# 2_MCU_schdoc.net
KiCad netlist of a schematic drawn in Altium Designer
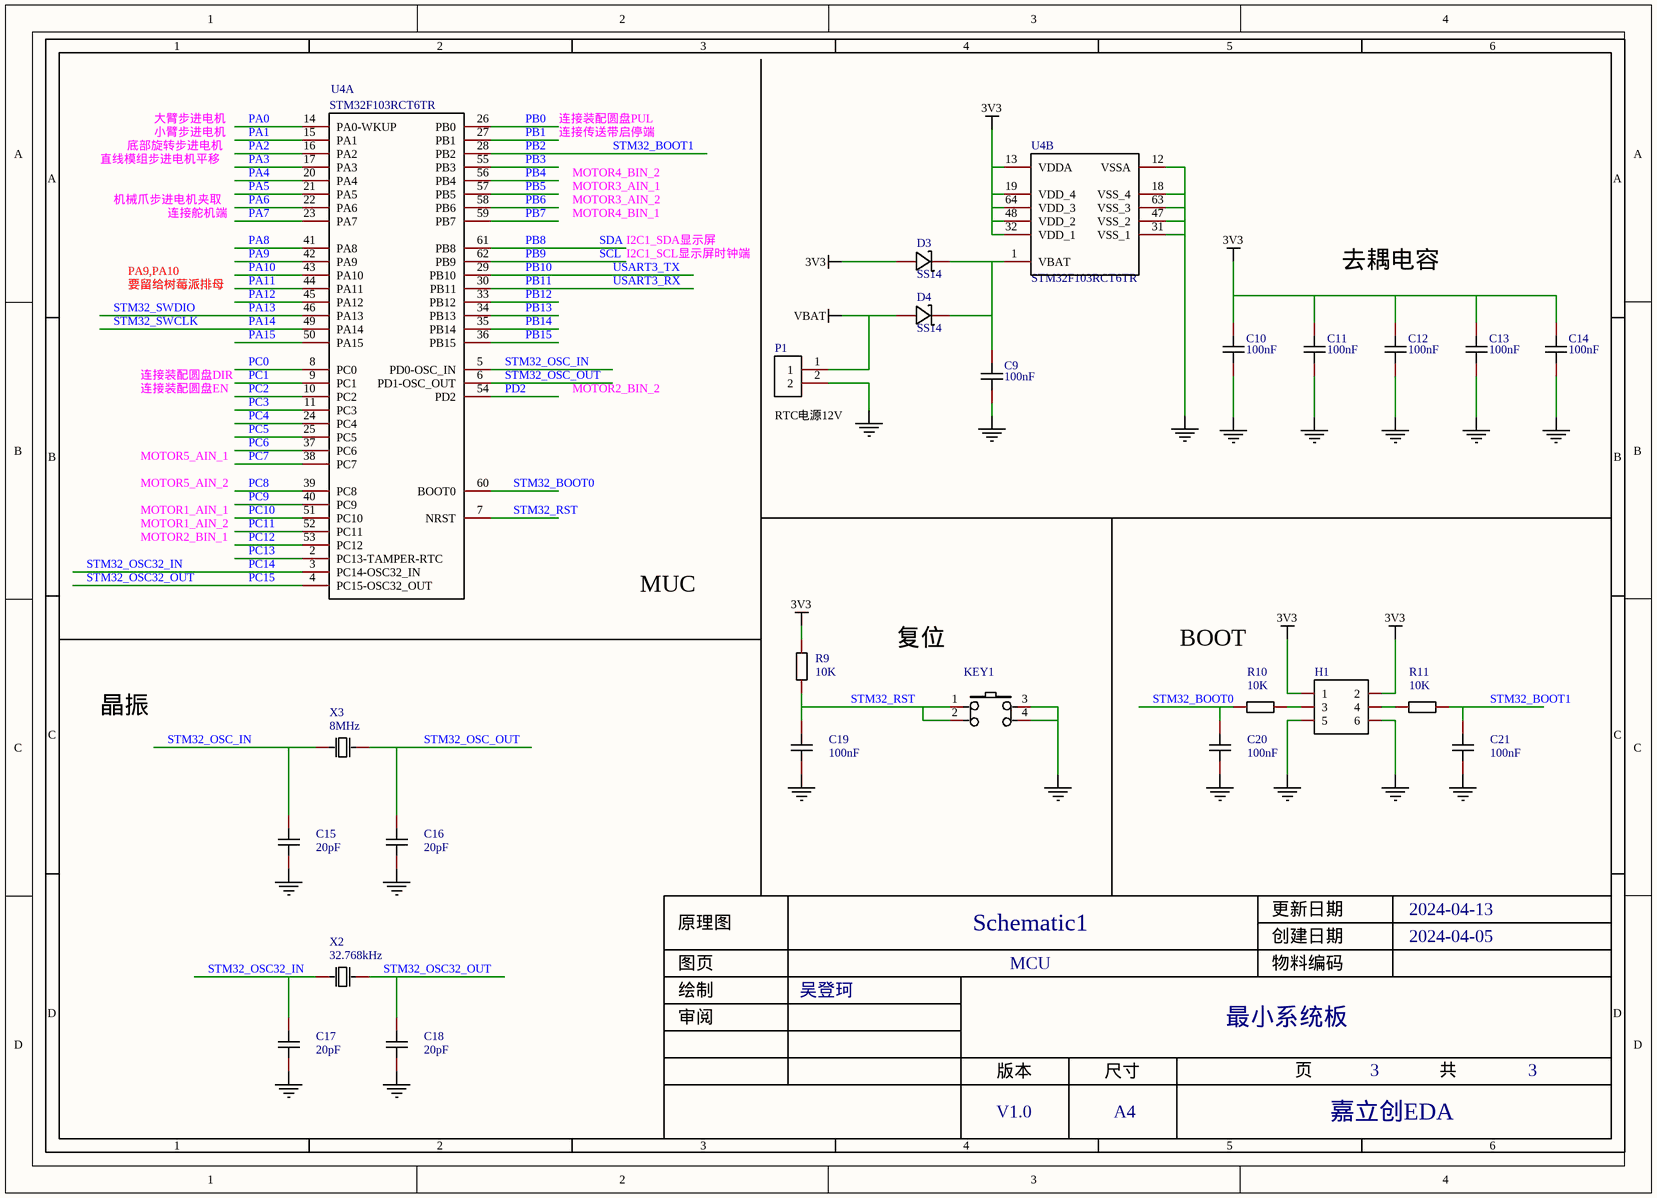
[diagram p0: 2_MCU.schdoc.schdoc]

(export (version "E")
  (design (tool "Eeschema 10.0.6"))
  (components
    (comp (ref "C9")
      (value "100nF")
      (fields (field (name "NAME") "100nF"))
      (libsource (lib "altium-import") (part "root_1_CAP_0603_"))
    )
    (comp (ref "C10")
      (value "100nF")
      (fields (field (name "NAME") "100nF"))
      (libsource (lib "altium-import") (part "root_1_CAP_0603_"))
    )
    (comp (ref "C11")
      (value "100nF")
      (fields (field (name "NAME") "100nF"))
      (libsource (lib "altium-import") (part "root_1_CAP_0603_"))
    )
    (comp (ref "C12")
      (value "100nF")
      (fields (field (name "NAME") "100nF"))
      (libsource (lib "altium-import") (part "root_1_CAP_0603_"))
    )
    (comp (ref "C13")
      (value "100nF")
      (fields (field (name "NAME") "100nF"))
      (libsource (lib "altium-import") (part "root_1_CAP_0603_"))
    )
    (comp (ref "C14")
      (value "100nF")
      (fields (field (name "NAME") "100nF"))
      (libsource (lib "altium-import") (part "root_1_CAP_0603_"))
    )
    (comp (ref "C15")
      (value "20pF")
      (fields (field (name "NAME") "20pF"))
      (libsource (lib "altium-import") (part "root_1_CAP_0603_"))
    )
    (comp (ref "C16")
      (value "20pF")
      (fields (field (name "NAME") "20pF"))
      (libsource (lib "altium-import") (part "root_1_CAP_0603_"))
    )
    (comp (ref "C17")
      (value "20pF")
      (fields (field (name "NAME") "20pF"))
      (libsource (lib "altium-import") (part "root_1_CAP_0603_"))
    )
    (comp (ref "C18")
      (value "20pF")
      (fields (field (name "NAME") "20pF"))
      (libsource (lib "altium-import") (part "root_1_CAP_0603_"))
    )
    (comp (ref "C19")
      (value "100nF")
      (fields (field (name "NAME") "100nF"))
      (libsource (lib "altium-import") (part "root_1_CAP_0603_"))
    )
    (comp (ref "C20")
      (value "100nF")
      (fields (field (name "NAME") "100nF"))
      (libsource (lib "altium-import") (part "root_1_CAP_0603_"))
    )
    (comp (ref "C21")
      (value "100nF")
      (fields (field (name "NAME") "100nF"))
      (libsource (lib "altium-import") (part "root_1_CAP_0603_"))
    )
    (comp (ref "D3")
      (value "SS14")
      (description "正向压降(Vf):500mV@1A;直流反向耐压(Vr):40V;平均整流电流(Io):1A;")
      (fields (field (name "NAME") "SS14") (field (name "MANUFACTURER") "onsemi(安森美)"))
      (libsource (lib "altium-import") (part "root_2_SS14_C83852_"))
    )
    (comp (ref "D4")
      (value "SS14")
      (description "正向压降(Vf):500mV@1A;直流反向耐压(Vr):40V;平均整流电流(Io):1A;")
      (fields (field (name "NAME") "SS14") (field (name "MANUFACTURER") "onsemi(安森美)"))
      (libsource (lib "altium-import") (part "root_2_SS14_C83852_"))
    )
    (comp (ref "H1")
      (value "HDR-F_2.54_2x3")
      (libsource (lib "altium-import") (part "root_0_HDR-F_2.54_2x3_"))
    )
    (comp (ref "KEY1")
      (value "6x6x6塑料头")
      (description "开关长度:6mm;开关宽度:6mm;开关高度:6mm;机械寿命:-;")
      (fields (field (name "MANUFACTURER") "国产"))
      (libsource (lib "altium-import") (part "root_0_6x6x6塑料头_"))
    )
    (comp (ref "P1")
      (value "WJ500V-5.08-2P")
      (fields (field (name "MANUFACTURER") "KANGNEX(康奈克斯电气)"))
      (libsource (lib "altium-import") (part "root_3_mirrored_WJ500V-5.08-2P_"))
    )
    (comp (ref "R9")
      (value "10K")
      (fields (field (name "NAME") "10K"))
      (libsource (lib "altium-import") (part "root_1_Res_0603_"))
    )
    (comp (ref "R10")
      (value "10K")
      (fields (field (name "NAME") "10K"))
      (libsource (lib "altium-import") (part "root_0_Res_0603_"))
    )
    (comp (ref "R11")
      (value "10K")
      (fields (field (name "NAME") "10K"))
      (libsource (lib "altium-import") (part "root_0_Res_0603_"))
    )
    (comp (ref "U4")
      (value "STM32F103RCT6TR")
      (description "CPU内核:CM3;程序存储容量:256KB;RAM总容量:48KB;GPIO端口数量:51;工作电压范围:2V~3.6V;CPU最大主频:72MHz;程序存储器类型:FLASH;")
      (fields (field (name "NAME") "STM32F103RCT6TR") (field (name "MANUFACTURER") "ST(意法半导体)"))
      (libsource (lib "altium-import") (part "root_2_mirrored_STM32F103RCT6TR_"))
    )
    (comp (ref "X2")
      (value "32.768kHz")
      (description "晶振类型:-;频率:-;外接负载电容:-;")
      (fields
        (field (name "NAME") "32.768kHz")
        (field (name "MANUFACTURER") "KDS(大真空)")
        (field (name "MANUFACTURER PART") "DST310S 32.768KHz")
      )
      (libsource (lib "altium-import") (part "root_0_DST310S 32.768KHz_"))
    )
    (comp (ref "X3")
      (value "8MHz")
      (description "晶振类型:贴片晶振;频率:8MHz;常温频差:±10ppm;外接负载电容:20pF;频率稳定度(全温):±20ppm;")
      (fields
        (field (name "NAME") "8MHz")
        (field (name "MANUFACTURER") "YXC(扬兴晶振)")
        (field (name "MANUFACTURER PART") "X50328MSB2GI")
      )
      (libsource (lib "altium-import") (part "root_0_X50328MSB2GI_"))
    )
  )
  (nets
    (net (code "1") (name "/PA0") (class "Default")
      (node (ref "U4") (pin "14") (pinfunction "PA0-WKUP_14") (pintype "passive"))
    )
    (net (code "2") (name "/PA1") (class "Default")
      (node (ref "U4") (pin "15") (pinfunction "PA1_15") (pintype "passive"))
    )
    (net (code "3") (name "/PA2") (class "Default")
      (node (ref "U4") (pin "16") (pinfunction "PA2_16") (pintype "passive"))
    )
    (net (code "4") (name "/PA3") (class "Default")
      (node (ref "U4") (pin "17") (pinfunction "PA3_17") (pintype "passive"))
    )
    (net (code "5") (name "/PA4") (class "Default")
      (node (ref "U4") (pin "20") (pinfunction "PA4_20") (pintype "passive"))
    )
    (net (code "6") (name "/PA5") (class "Default")
      (node (ref "U4") (pin "21") (pinfunction "PA5_21") (pintype "passive"))
    )
    (net (code "7") (name "/PA6") (class "Default")
      (node (ref "U4") (pin "22") (pinfunction "PA6_22") (pintype "passive"))
    )
    (net (code "8") (name "/PA7") (class "Default")
      (node (ref "U4") (pin "23") (pinfunction "PA7_23") (pintype "passive"))
    )
    (net (code "9") (name "/PA8") (class "Default")
      (node (ref "U4") (pin "41") (pinfunction "PA8_41") (pintype "passive"))
    )
    (net (code "10") (name "/PA9") (class "Default")
      (node (ref "U4") (pin "42") (pinfunction "PA9_42") (pintype "passive"))
    )
    (net (code "11") (name "/PA10") (class "Default")
      (node (ref "U4") (pin "43") (pinfunction "PA10_43") (pintype "passive"))
    )
    (net (code "12") (name "/PA11") (class "Default")
      (node (ref "U4") (pin "44") (pinfunction "PA11_44") (pintype "passive"))
    )
    (net (code "13") (name "/PA12") (class "Default")
      (node (ref "U4") (pin "45") (pinfunction "PA12_45") (pintype "passive"))
    )
    (net (code "14") (name "/PA13") (class "Default")
      (node (ref "U4") (pin "46") (pinfunction "PA13_46") (pintype "passive"))
    )
    (net (code "15") (name "/PA14") (class "Default")
      (node (ref "U4") (pin "49") (pinfunction "PA14_49") (pintype "passive"))
    )
    (net (code "16") (name "/PA15") (class "Default")
      (node (ref "U4") (pin "50") (pinfunction "PA15_50") (pintype "passive"))
    )
    (net (code "17") (name "/PB0") (class "Default")
      (node (ref "U4") (pin "26") (pinfunction "PB0_26") (pintype "passive"))
    )
    (net (code "18") (name "/PB1") (class "Default")
      (node (ref "U4") (pin "27") (pinfunction "PB1_27") (pintype "passive"))
    )
    (net (code "19") (name "/PB2") (class "Default")
      (node (ref "C21") (pin "2") (pinfunction "2_2") (pintype "passive"))
      (node (ref "R11") (pin "2") (pinfunction "2_2") (pintype "passive"))
      (node (ref "U4") (pin "28") (pinfunction "PB2_28") (pintype "passive"))
    )
    (net (code "20") (name "/PB3") (class "Default")
      (node (ref "U4") (pin "55") (pinfunction "PB3_55") (pintype "passive"))
    )
    (net (code "21") (name "/PB4") (class "Default")
      (node (ref "U4") (pin "56") (pinfunction "PB4_56") (pintype "passive"))
    )
    (net (code "22") (name "/PB5") (class "Default")
      (node (ref "U4") (pin "57") (pinfunction "PB5_57") (pintype "passive"))
    )
    (net (code "23") (name "/PB6") (class "Default")
      (node (ref "U4") (pin "58") (pinfunction "PB6_58") (pintype "passive"))
    )
    (net (code "24") (name "/PB7") (class "Default")
      (node (ref "U4") (pin "59") (pinfunction "PB7_59") (pintype "passive"))
    )
    (net (code "25") (name "/PB8") (class "Default")
      (node (ref "U4") (pin "61") (pinfunction "PB8_61") (pintype "passive"))
    )
    (net (code "26") (name "/PB9") (class "Default")
      (node (ref "U4") (pin "62") (pinfunction "PB9_62") (pintype "passive"))
    )
    (net (code "27") (name "/PB10") (class "Default")
      (node (ref "U4") (pin "29") (pinfunction "PB10_29") (pintype "passive"))
    )
    (net (code "28") (name "/PB11") (class "Default")
      (node (ref "U4") (pin "30") (pinfunction "PB11_30") (pintype "passive"))
    )
    (net (code "29") (name "/PB12") (class "Default")
      (node (ref "U4") (pin "33") (pinfunction "PB12_33") (pintype "passive"))
    )
    (net (code "30") (name "/PB13") (class "Default")
      (node (ref "U4") (pin "34") (pinfunction "PB13_34") (pintype "passive"))
    )
    (net (code "31") (name "/PB14") (class "Default")
      (node (ref "U4") (pin "35") (pinfunction "PB14_35") (pintype "passive"))
    )
    (net (code "32") (name "/PB15") (class "Default")
      (node (ref "U4") (pin "36") (pinfunction "PB15_36") (pintype "passive"))
    )
    (net (code "33") (name "/PC0") (class "Default")
      (node (ref "U4") (pin "8") (pinfunction "PC0_8") (pintype "passive"))
    )
    (net (code "34") (name "/PC1") (class "Default")
      (node (ref "U4") (pin "9") (pinfunction "PC1_9") (pintype "passive"))
    )
    (net (code "35") (name "/PC2") (class "Default")
      (node (ref "U4") (pin "10") (pinfunction "PC2_10") (pintype "passive"))
    )
    (net (code "36") (name "/PC3") (class "Default")
      (node (ref "U4") (pin "11") (pinfunction "PC3_11") (pintype "passive"))
    )
    (net (code "37") (name "/PC4") (class "Default")
      (node (ref "U4") (pin "24") (pinfunction "PC4_24") (pintype "passive"))
    )
    (net (code "38") (name "/PC5") (class "Default")
      (node (ref "U4") (pin "25") (pinfunction "PC5_25") (pintype "passive"))
    )
    (net (code "39") (name "/PC6") (class "Default")
      (node (ref "U4") (pin "37") (pinfunction "PC6_37") (pintype "passive"))
    )
    (net (code "40") (name "/PC7") (class "Default")
      (node (ref "U4") (pin "38") (pinfunction "PC7_38") (pintype "passive"))
    )
    (net (code "41") (name "/PC8") (class "Default")
      (node (ref "U4") (pin "39") (pinfunction "PC8_39") (pintype "passive"))
    )
    (net (code "42") (name "/PC9") (class "Default")
      (node (ref "U4") (pin "40") (pinfunction "PC9_40") (pintype "passive"))
    )
    (net (code "43") (name "/PC10") (class "Default")
      (node (ref "U4") (pin "51") (pinfunction "PC10_51") (pintype "passive"))
    )
    (net (code "44") (name "/PC11") (class "Default")
      (node (ref "U4") (pin "52") (pinfunction "PC11_52") (pintype "passive"))
    )
    (net (code "45") (name "/PC12") (class "Default")
      (node (ref "U4") (pin "53") (pinfunction "PC12_53") (pintype "passive"))
    )
    (net (code "46") (name "/PC13") (class "Default")
      (node (ref "U4") (pin "2") (pinfunction "PC13-TAMPER-RTC_2") (pintype "passive"))
    )
    (net (code "47") (name "/PC14") (class "Default")
      (node (ref "C17") (pin "2") (pinfunction "2_2") (pintype "passive"))
      (node (ref "U4") (pin "3") (pinfunction "PC14-OSC32_IN_3") (pintype "passive"))
      (node (ref "X2") (pin "1") (pinfunction "OSC1_1") (pintype "passive"))
    )
    (net (code "48") (name "/PC15") (class "Default")
      (node (ref "C18") (pin "2") (pinfunction "2_2") (pintype "passive"))
      (node (ref "U4") (pin "4") (pinfunction "PC15-OSC32_OUT_4") (pintype "passive"))
      (node (ref "X2") (pin "2") (pinfunction "OSC2_2") (pintype "passive"))
    )
    (net (code "49") (name "/PD2") (class "Default")
      (node (ref "U4") (pin "54") (pinfunction "PD2_54") (pintype "passive"))
    )
    (net (code "50") (name "/STM32_BOOT0") (class "Default")
      (node (ref "C20") (pin "2") (pinfunction "2_2") (pintype "passive"))
      (node (ref "R10") (pin "1") (pinfunction "1_1") (pintype "passive"))
      (node (ref "U4") (pin "60") (pinfunction "BOOT0_60") (pintype "passive"))
    )
    (net (code "51") (name "/STM32_OSC_IN") (class "Default")
      (node (ref "C15") (pin "2") (pinfunction "2_2") (pintype "passive"))
      (node (ref "U4") (pin "5") (pinfunction "PD0-OSC_IN_5") (pintype "passive"))
      (node (ref "X3") (pin "1") (pinfunction "OSC1_1") (pintype "passive"))
    )
    (net (code "52") (name "/STM32_OSC_OUT") (class "Default")
      (node (ref "C16") (pin "2") (pinfunction "2_2") (pintype "passive"))
      (node (ref "U4") (pin "6") (pinfunction "PD1-OSC_OUT_6") (pintype "passive"))
      (node (ref "X3") (pin "2") (pinfunction "OSC2_2") (pintype "passive"))
    )
    (net (code "53") (name "/STM32_RST") (class "Default")
      (node (ref "C19") (pin "2") (pinfunction "2_2") (pintype "passive"))
      (node (ref "KEY1") (pin "1") (pinfunction "1_1") (pintype "passive"))
      (node (ref "KEY1") (pin "2") (pinfunction "2_2") (pintype "passive"))
      (node (ref "R9") (pin "1") (pinfunction "1_1") (pintype "passive"))
      (node (ref "U4") (pin "7") (pinfunction "NRST_7") (pintype "passive"))
    )
    (net (code "54") (name "3V3") (class "Default")
      (node (ref "C10") (pin "2") (pinfunction "2_2") (pintype "passive"))
      (node (ref "C11") (pin "2") (pinfunction "2_2") (pintype "passive"))
      (node (ref "C12") (pin "2") (pinfunction "2_2") (pintype "passive"))
      (node (ref "C13") (pin "2") (pinfunction "2_2") (pintype "passive"))
      (node (ref "C14") (pin "2") (pinfunction "2_2") (pintype "passive"))
      (node (ref "D3") (pin "2") (pinfunction "A_2") (pintype "passive"))
      (node (ref "H1") (pin "1") (pinfunction "1_1") (pintype "passive"))
      (node (ref "H1") (pin "2") (pinfunction "2_2") (pintype "passive"))
      (node (ref "R9") (pin "2") (pinfunction "2_2") (pintype "passive"))
      (node (ref "U4") (pin "13") (pinfunction "VDDA_13") (pintype "passive"))
      (node (ref "U4") (pin "19") (pinfunction "VDD_4_19") (pintype "passive"))
      (node (ref "U4") (pin "32") (pinfunction "VDD_1_32") (pintype "passive"))
      (node (ref "U4") (pin "48") (pinfunction "VDD_2_48") (pintype "passive"))
      (node (ref "U4") (pin "64") (pinfunction "VDD_3_64") (pintype "passive"))
    )
    (net (code "55") (name "<NO NET>") (class "Default")
      (node (ref "C10") (pin "1") (pinfunction "1_1") (pintype "passive"))
      (node (ref "C11") (pin "1") (pinfunction "1_1") (pintype "passive"))
      (node (ref "C12") (pin "1") (pinfunction "1_1") (pintype "passive"))
      (node (ref "C13") (pin "1") (pinfunction "1_1") (pintype "passive"))
      (node (ref "C14") (pin "1") (pinfunction "1_1") (pintype "passive"))
      (node (ref "C15") (pin "1") (pinfunction "1_1") (pintype "passive"))
      (node (ref "C16") (pin "1") (pinfunction "1_1") (pintype "passive"))
      (node (ref "C17") (pin "1") (pinfunction "1_1") (pintype "passive"))
      (node (ref "C18") (pin "1") (pinfunction "1_1") (pintype "passive"))
      (node (ref "C19") (pin "1") (pinfunction "1_1") (pintype "passive"))
      (node (ref "C20") (pin "1") (pinfunction "1_1") (pintype "passive"))
      (node (ref "C21") (pin "1") (pinfunction "1_1") (pintype "passive"))
      (node (ref "C9") (pin "1") (pinfunction "1_1") (pintype "passive"))
      (node (ref "H1") (pin "5") (pinfunction "5_5") (pintype "passive"))
      (node (ref "H1") (pin "6") (pinfunction "6_6") (pintype "passive"))
      (node (ref "KEY1") (pin "3") (pinfunction "3_3") (pintype "passive"))
      (node (ref "KEY1") (pin "4") (pinfunction "4_4") (pintype "passive"))
      (node (ref "P1") (pin "2") (pinfunction "2_2") (pintype "passive"))
      (node (ref "U4") (pin "12") (pinfunction "VSSA_12") (pintype "passive"))
      (node (ref "U4") (pin "18") (pinfunction "VSS_4_18") (pintype "passive"))
      (node (ref "U4") (pin "31") (pinfunction "VSS_1_31") (pintype "passive"))
      (node (ref "U4") (pin "47") (pinfunction "VSS_2_47") (pintype "passive"))
      (node (ref "U4") (pin "63") (pinfunction "VSS_3_63") (pintype "passive"))
    )
    (net (code "56") (name "Net-(D3-K)") (class "Default")
      (node (ref "C9") (pin "2") (pinfunction "2_2") (pintype "passive"))
      (node (ref "D3") (pin "1") (pinfunction "K_1") (pintype "passive"))
      (node (ref "D4") (pin "1") (pinfunction "K_1") (pintype "passive"))
      (node (ref "U4") (pin "1") (pinfunction "VBAT_1") (pintype "passive"))
    )
    (net (code "57") (name "Net-(H1-Pad3)") (class "Default")
      (node (ref "H1") (pin "3") (pinfunction "3_3") (pintype "passive"))
      (node (ref "R10") (pin "2") (pinfunction "2_2") (pintype "passive"))
    )
    (net (code "58") (name "Net-(H1-Pad4)") (class "Default")
      (node (ref "H1") (pin "4") (pinfunction "4_4") (pintype "passive"))
      (node (ref "R11") (pin "1") (pinfunction "1_1") (pintype "passive"))
    )
    (net (code "59") (name "VBAT") (class "Default")
      (node (ref "D4") (pin "2") (pinfunction "A_2") (pintype "passive"))
      (node (ref "P1") (pin "1") (pinfunction "1_1") (pintype "passive"))
    )
  )
)
